# Main.net
KiCad netlist of a schematic drawn in Altium Designer
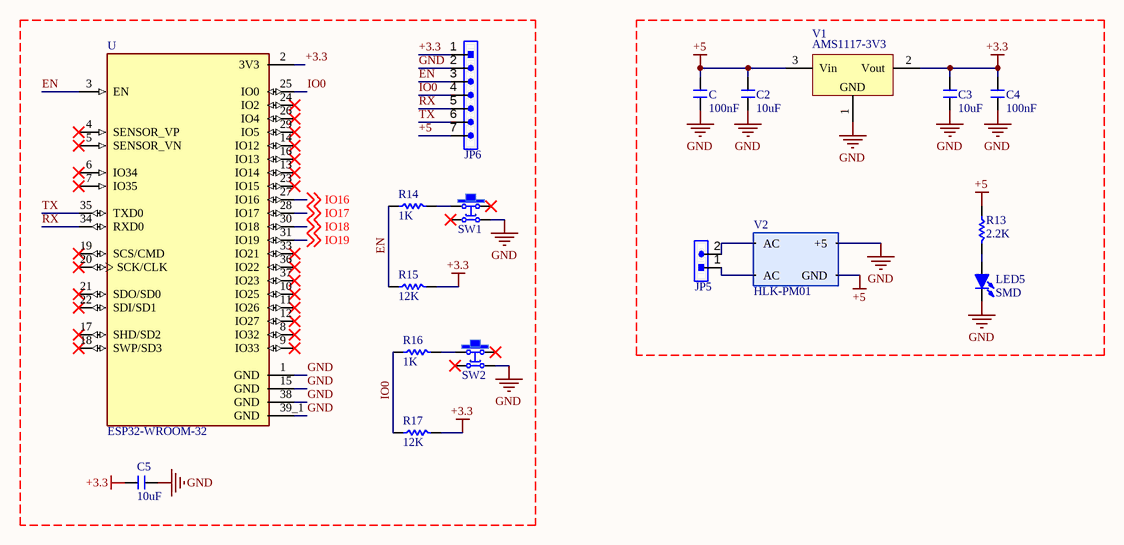
[diagram p0: Main.SchDoc]

(export (version "E")
  (design (tool "Eeschema 10.0.6"))
  (components
    (comp (ref "C")
      (value "100nF")
      (footprint "C 0805")
      (description "Non-polar patch capacitor")
      (fields (field (name "版权归属") "源创客"))
      (libsource (lib "Passive (Resistor-Capacitor-Inductor-Veristor-Ferrite)") (part "C"))
    )
    (comp (ref "C2")
      (value "10uF")
      (footprint "C 0805")
      (description "Non-polar patch capacitor")
      (fields (field (name "版权归属") "源创客"))
      (libsource (lib "Passive (Resistor-Capacitor-Inductor-Veristor-Ferrite)") (part "C"))
    )
    (comp (ref "C3")
      (value "10uF")
      (footprint "C 0805")
      (description "Non-polar patch capacitor")
      (fields (field (name "版权归属") "源创客"))
      (libsource (lib "Passive (Resistor-Capacitor-Inductor-Veristor-Ferrite)") (part "C"))
    )
    (comp (ref "C4")
      (value "100nF")
      (footprint "C 0805")
      (description "Non-polar patch capacitor")
      (fields (field (name "版权归属") "源创客"))
      (libsource (lib "Passive (Resistor-Capacitor-Inductor-Veristor-Ferrite)") (part "C"))
    )
    (comp (ref "C5")
      (value "10uF")
      (footprint "C 0805")
      (description "Non-polar patch capacitor")
      (fields (field (name "版权归属") "源创客"))
      (libsource (lib "Passive (Resistor-Capacitor-Inductor-Veristor-Ferrite)") (part "C"))
    )
    (comp (ref "JP5")
      (value "HDR-1X2")
      (footprint "KF2EDGK-2P")
      (description "2P Connector")
      (fields (field (name "版权归属") "源创客"))
      (libsource (lib "Connectors") (part "Header 2"))
    )
    (comp (ref "JP6")
      (value "HDR-1X7")
      (footprint "HDR-1X7")
      (description "7P Connector")
      (fields (field (name "版权归属") "源创客"))
      (libsource (lib "Connectors") (part "Header 7"))
    )
    (comp (ref "LED5")
      (value "SMD")
      (footprint "LED 0805R")
      (description "RED LED")
      (fields (field (name "版权归属") "源创客"))
      (libsource (lib "LED") (part "LED-SMD"))
    )
    (comp (ref "R13")
      (value "2.2K")
      (footprint "R 0805")
      (description "Chip resistor")
      (fields (field (name "版权归属") "源创客"))
      (libsource (lib "Passive (Resistor-Capacitor-Inductor-Veristor-Ferrite)") (part "R"))
    )
    (comp (ref "R14")
      (value "1K")
      (footprint "R 0805")
      (description "Chip resistor")
      (fields (field (name "版权归属") "源创客"))
      (libsource (lib "AltiumDesigner PCB Library") (part "R"))
    )
    (comp (ref "R15")
      (value "12K")
      (footprint "R 0805")
      (description "Chip resistor")
      (fields (field (name "版权归属") "源创客"))
      (libsource (lib "AltiumDesigner PCB Library") (part "R"))
    )
    (comp (ref "R16")
      (value "1K")
      (footprint "R 0805")
      (description "Chip resistor")
      (fields (field (name "版权归属") "源创客"))
      (libsource (lib "AltiumDesigner PCB Library") (part "R"))
    )
    (comp (ref "R17")
      (value "12K")
      (footprint "R 0805")
      (description "Chip resistor")
      (fields (field (name "版权归属") "源创客"))
      (libsource (lib "AltiumDesigner PCB Library") (part "R"))
    )
    (comp (ref "SW1")
      (value "Reset Key")
      (footprint "TSW SMD-6*6*4.3")
      (description "Patch 6x6 tact switch")
      (fields (field (name "版权归属") "源创客"))
      (libsource (lib "Button") (part "TSW SMD-6x6"))
    )
    (comp (ref "SW2")
      (value "Reset Key")
      (footprint "TSW SMD-6*6*4.3")
      (description "Patch 6x6 tact switch")
      (fields (field (name "版权归属") "源创客"))
      (libsource (lib "Button") (part "TSW SMD-6x6"))
    )
    (comp (ref "U")
      (value "ESP32-WROOM-32")
      (footprint "MODULE_ESP32-WROOM-32")
      (description "Bluetooth, WiFi Transceiver Module 2.4GHz ~ 2.5GHz Surface Mount")
      (fields (field (name "MF") "Espressif Systems") (field (name "DIGI-KEY_PART_NUMBER") "1904-1010-1-ND"))
      (libsource (lib "ESP32-WROOM-32") (part "ESP32-WROOM-32"))
    )
    (comp (ref "V1")
      (value "AMS1117-3V3")
      (footprint "SOT223_L")
      (description "Three-terminal regulator chip")
      (fields (field (name "版权归属") "源创客"))
      (libsource (lib "Integrated Circuit") (part "AMS1117"))
    )
    (comp (ref "V2")
      (value "HLK-PM01")
      (footprint "HLKPM01")
      (fields (field (name "MF") "Hi-link") (field (name "MP") "hlk-pm01"))
      (libsource (lib "HLK-PM01") (part "HLK-PM01"))
    )
  )
  (nets
    (net (code "1") (name "+3.3") (class "Default")
      (node (ref "C3") (pin "2") (pinfunction "2_2") (pintype "passive"))
      (node (ref "C4") (pin "2") (pinfunction "2_2") (pintype "passive"))
      (node (ref "C5") (pin "2") (pinfunction "2_2") (pintype "passive"))
      (node (ref "JP6") (pin "1") (pintype "passive"))
      (node (ref "R15") (pin "2") (pinfunction "2_2") (pintype "passive"))
      (node (ref "R17") (pin "2") (pinfunction "2_2") (pintype "passive"))
      (node (ref "U") (pin "2") (pinfunction "3V3_2") (pintype "power_in"))
      (node (ref "V1") (pin "2") (pinfunction "Vout_2") (pintype "passive"))
    )
    (net (code "2") (name "+5") (class "Default")
      (node (ref "C") (pin "2") (pinfunction "2_2") (pintype "passive"))
      (node (ref "C2") (pin "2") (pinfunction "2_2") (pintype "passive"))
      (node (ref "JP6") (pin "7") (pintype "passive"))
      (node (ref "R13") (pin "1") (pinfunction "1_1") (pintype "passive"))
      (node (ref "V1") (pin "3") (pinfunction "Vin_3") (pintype "passive"))
      (node (ref "V2") (pin "4") (pinfunction "GND_4") (pintype "output"))
    )
    (net (code "3") (name "/EN") (class "Default")
      (node (ref "JP6") (pin "3") (pintype "passive"))
      (node (ref "R14") (pin "1") (pinfunction "1_1") (pintype "passive"))
      (node (ref "R15") (pin "1") (pinfunction "1_1") (pintype "passive"))
      (node (ref "U") (pin "3") (pinfunction "EN_3") (pintype "input"))
    )
    (net (code "4") (name "/IO0") (class "Default")
      (node (ref "JP6") (pin "4") (pintype "passive"))
      (node (ref "R16") (pin "1") (pinfunction "1_1") (pintype "passive"))
      (node (ref "R17") (pin "1") (pinfunction "1_1") (pintype "passive"))
      (node (ref "U") (pin "25") (pinfunction "IO0_25") (pintype "bidirectional"))
    )
    (net (code "5") (name "/RX") (class "Default")
      (node (ref "JP6") (pin "5") (pintype "passive"))
      (node (ref "U") (pin "34") (pinfunction "RXD0_34") (pintype "bidirectional"))
    )
    (net (code "6") (name "/TX") (class "Default")
      (node (ref "JP6") (pin "6") (pintype "passive"))
      (node (ref "U") (pin "35") (pinfunction "TXD0_35") (pintype "bidirectional"))
    )
    (net (code "7") (name "GND") (class "Default")
      (node (ref "C") (pin "1") (pinfunction "1_1") (pintype "passive"))
      (node (ref "C2") (pin "1") (pinfunction "1_1") (pintype "passive"))
      (node (ref "C3") (pin "1") (pinfunction "1_1") (pintype "passive"))
      (node (ref "C4") (pin "1") (pinfunction "1_1") (pintype "passive"))
      (node (ref "C5") (pin "1") (pinfunction "1_1") (pintype "passive"))
      (node (ref "JP6") (pin "2") (pintype "passive"))
      (node (ref "LED5") (pin "2") (pinfunction "K_2") (pintype "passive"))
      (node (ref "SW1") (pin "3") (pinfunction "3_3") (pintype "passive"))
      (node (ref "SW2") (pin "3") (pinfunction "3_3") (pintype "passive"))
      (node (ref "U") (pin "1") (pinfunction "GND_1") (pintype "power_in"))
      (node (ref "U") (pin "15") (pinfunction "GND_15") (pintype "power_in"))
      (node (ref "U") (pin "38") (pinfunction "GND_38") (pintype "power_in"))
      (node (ref "U") (pin "39_1") (pinfunction "GND_39_1") (pintype "power_in"))
      (node (ref "V1") (pin "1") (pinfunction "GND_1") (pintype "passive"))
      (node (ref "V2") (pin "3") (pinfunction "+5_3") (pintype "output"))
    )
    (net (code "8") (name "IO16") (class "Default")
      (node (ref "U") (pin "27") (pinfunction "IO16_27") (pintype "bidirectional"))
    )
    (net (code "9") (name "IO17") (class "Default")
      (node (ref "U") (pin "28") (pinfunction "IO17_28") (pintype "bidirectional"))
    )
    (net (code "10") (name "IO18") (class "Default")
      (node (ref "U") (pin "30") (pinfunction "IO18_30") (pintype "bidirectional"))
    )
    (net (code "11") (name "IO19") (class "Default")
      (node (ref "U") (pin "31") (pinfunction "IO19_31") (pintype "bidirectional"))
    )
    (net (code "12") (name "Net-(JP5-Pad1)") (class "Default")
      (node (ref "JP5") (pin "1") (pintype "passive"))
      (node (ref "V2") (pin "2") (pinfunction "AC_2") (pintype "input"))
    )
    (net (code "13") (name "Net-(JP5-Pad2)") (class "Default")
      (node (ref "JP5") (pin "2") (pintype "passive"))
      (node (ref "V2") (pin "1") (pinfunction "AC_1") (pintype "input"))
    )
    (net (code "14") (name "Net-(LED5-A)") (class "Default")
      (node (ref "LED5") (pin "1") (pinfunction "A_1") (pintype "passive"))
      (node (ref "R13") (pin "2") (pinfunction "2_2") (pintype "passive"))
    )
    (net (code "15") (name "Net-(R14-Pad2)") (class "Default")
      (node (ref "R14") (pin "2") (pinfunction "2_2") (pintype "passive"))
      (node (ref "SW1") (pin "1") (pinfunction "1_1") (pintype "passive"))
    )
    (net (code "16") (name "Net-(R16-Pad2)") (class "Default")
      (node (ref "R16") (pin "2") (pinfunction "2_2") (pintype "passive"))
      (node (ref "SW2") (pin "1") (pinfunction "1_1") (pintype "passive"))
    )
    (net (code "17") (name "unconnected-(SW1-Pad2)") (class "Default")
      (node (ref "SW1") (pin "2") (pinfunction "2_2") (pintype "passive+no_connect"))
    )
    (net (code "18") (name "unconnected-(SW1-Pad4)") (class "Default")
      (node (ref "SW1") (pin "4") (pinfunction "4_4") (pintype "passive+no_connect"))
    )
    (net (code "19") (name "unconnected-(SW2-Pad2)") (class "Default")
      (node (ref "SW2") (pin "2") (pinfunction "2_2") (pintype "passive+no_connect"))
    )
    (net (code "20") (name "unconnected-(SW2-Pad4)") (class "Default")
      (node (ref "SW2") (pin "4") (pinfunction "4_4") (pintype "passive+no_connect"))
    )
    (net (code "21") (name "unconnected-(U-IO2-Pad24)") (class "Default")
      (node (ref "U") (pin "24") (pinfunction "IO2_24") (pintype "bidirectional+no_connect"))
    )
    (net (code "22") (name "unconnected-(U-IO4-Pad26)") (class "Default")
      (node (ref "U") (pin "26") (pinfunction "IO4_26") (pintype "bidirectional+no_connect"))
    )
    (net (code "23") (name "unconnected-(U-IO5-Pad29)") (class "Default")
      (node (ref "U") (pin "29") (pinfunction "IO5_29") (pintype "bidirectional+no_connect"))
    )
    (net (code "24") (name "unconnected-(U-IO12-Pad14)") (class "Default")
      (node (ref "U") (pin "14") (pinfunction "IO12_14") (pintype "bidirectional+no_connect"))
    )
    (net (code "25") (name "unconnected-(U-IO13-Pad16)") (class "Default")
      (node (ref "U") (pin "16") (pinfunction "IO13_16") (pintype "bidirectional+no_connect"))
    )
    (net (code "26") (name "unconnected-(U-IO14-Pad13)") (class "Default")
      (node (ref "U") (pin "13") (pinfunction "IO14_13") (pintype "bidirectional+no_connect"))
    )
    (net (code "27") (name "unconnected-(U-IO15-Pad23)") (class "Default")
      (node (ref "U") (pin "23") (pinfunction "IO15_23") (pintype "bidirectional+no_connect"))
    )
    (net (code "28") (name "unconnected-(U-IO21-Pad33)") (class "Default")
      (node (ref "U") (pin "33") (pinfunction "IO21_33") (pintype "bidirectional+no_connect"))
    )
    (net (code "29") (name "unconnected-(U-IO22-Pad36)") (class "Default")
      (node (ref "U") (pin "36") (pinfunction "IO22_36") (pintype "bidirectional+no_connect"))
    )
    (net (code "30") (name "unconnected-(U-IO23-Pad37)") (class "Default")
      (node (ref "U") (pin "37") (pinfunction "IO23_37") (pintype "bidirectional+no_connect"))
    )
    (net (code "31") (name "unconnected-(U-IO25-Pad10)") (class "Default")
      (node (ref "U") (pin "10") (pinfunction "IO25_10") (pintype "bidirectional+no_connect"))
    )
    (net (code "32") (name "unconnected-(U-IO26-Pad11)") (class "Default")
      (node (ref "U") (pin "11") (pinfunction "IO26_11") (pintype "bidirectional+no_connect"))
    )
    (net (code "33") (name "unconnected-(U-IO27-Pad12)") (class "Default")
      (node (ref "U") (pin "12") (pinfunction "IO27_12") (pintype "bidirectional+no_connect"))
    )
    (net (code "34") (name "unconnected-(U-IO32-Pad8)") (class "Default")
      (node (ref "U") (pin "8") (pinfunction "IO32_8") (pintype "bidirectional+no_connect"))
    )
    (net (code "35") (name "unconnected-(U-IO33-Pad9)") (class "Default")
      (node (ref "U") (pin "9") (pinfunction "IO33_9") (pintype "bidirectional+no_connect"))
    )
    (net (code "36") (name "unconnected-(U-IO34-Pad6)") (class "Default")
      (node (ref "U") (pin "6") (pinfunction "IO34_6") (pintype "input+no_connect"))
    )
    (net (code "37") (name "unconnected-(U-IO35-Pad7)") (class "Default")
      (node (ref "U") (pin "7") (pinfunction "IO35_7") (pintype "input+no_connect"))
    )
    (net (code "38") (name "unconnected-(U-SCK{slash}CLK-Pad20)") (class "Default")
      (node (ref "U") (pin "20") (pinfunction "SCK/CLK_20") (pintype "bidirectional+no_connect"))
    )
    (net (code "39") (name "unconnected-(U-SCS{slash}CMD-Pad19)") (class "Default")
      (node (ref "U") (pin "19") (pinfunction "SCS/CMD_19") (pintype "bidirectional+no_connect"))
    )
    (net (code "40") (name "unconnected-(U-SDI{slash}SD1-Pad22)") (class "Default")
      (node (ref "U") (pin "22") (pinfunction "SDI/SD1_22") (pintype "bidirectional+no_connect"))
    )
    (net (code "41") (name "unconnected-(U-SDO{slash}SD0-Pad21)") (class "Default")
      (node (ref "U") (pin "21") (pinfunction "SDO/SD0_21") (pintype "bidirectional+no_connect"))
    )
    (net (code "42") (name "unconnected-(U-SENSOR_VN-Pad5)") (class "Default")
      (node (ref "U") (pin "5") (pinfunction "SENSOR_VN_5") (pintype "input+no_connect"))
    )
    (net (code "43") (name "unconnected-(U-SENSOR_VP-Pad4)") (class "Default")
      (node (ref "U") (pin "4") (pinfunction "SENSOR_VP_4") (pintype "input+no_connect"))
    )
    (net (code "44") (name "unconnected-(U-SHD{slash}SD2-Pad17)") (class "Default")
      (node (ref "U") (pin "17") (pinfunction "SHD/SD2_17") (pintype "bidirectional+no_connect"))
    )
    (net (code "45") (name "unconnected-(U-SWP{slash}SD3-Pad18)") (class "Default")
      (node (ref "U") (pin "18") (pinfunction "SWP/SD3_18") (pintype "bidirectional+no_connect"))
    )
  )
)
